# 6_dc_dc_5V_Payloads.net
KiCad netlist of a schematic drawn in Altium Designer
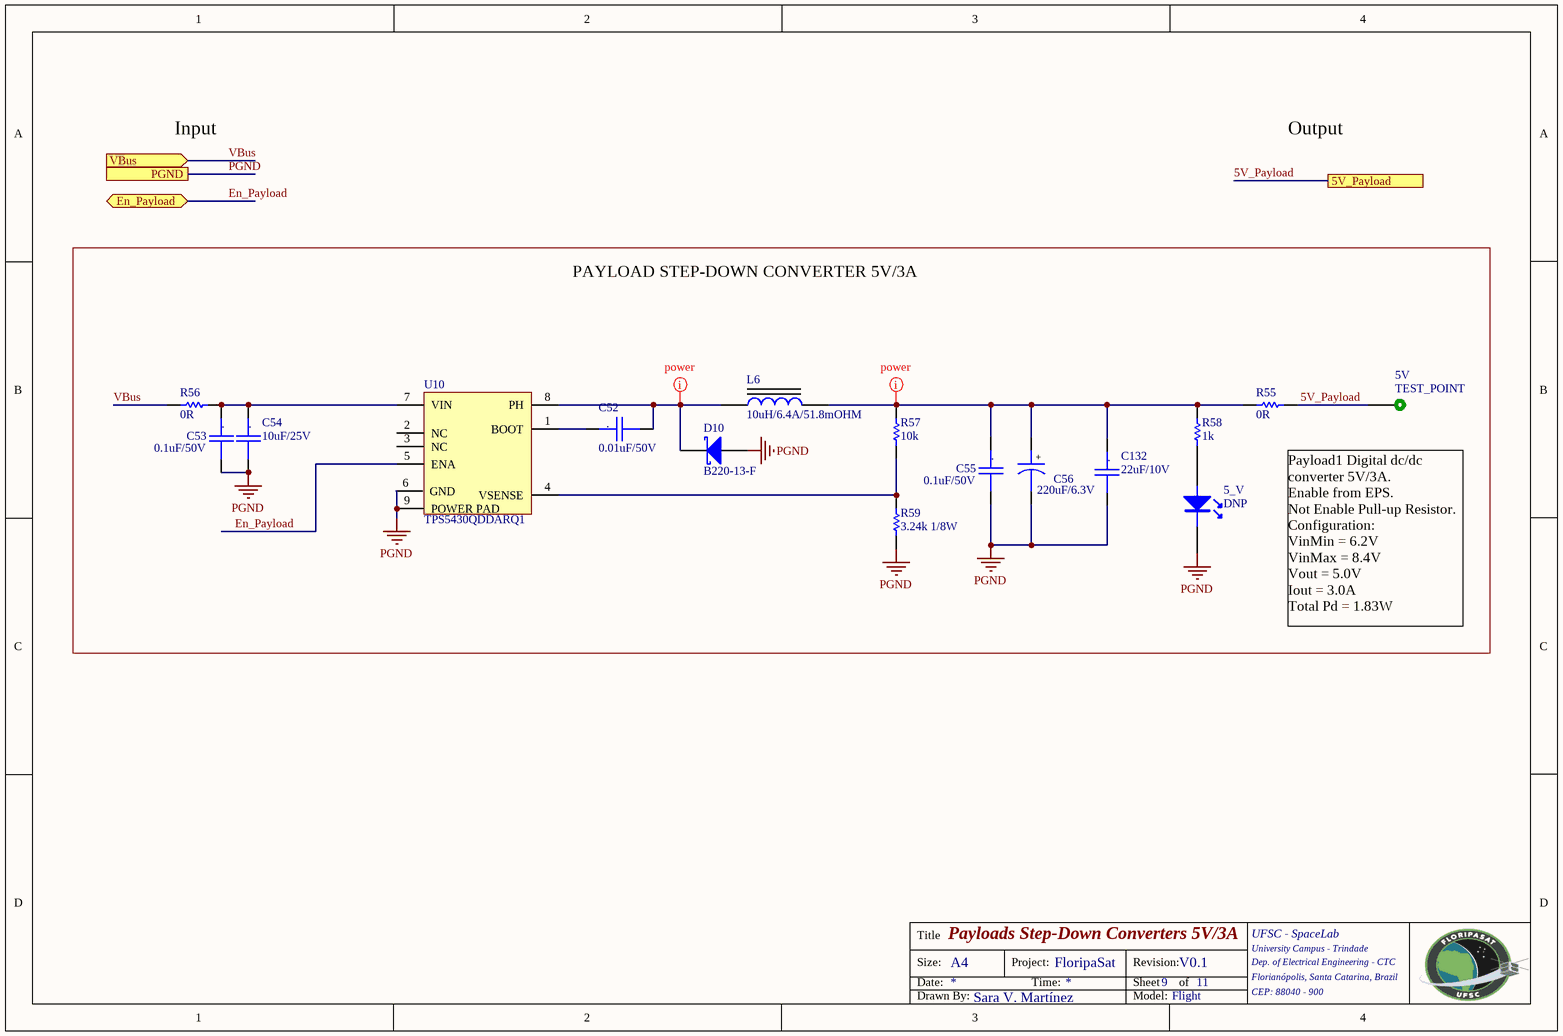
[diagram p0: 6_dc_dc_5V_Payloads.SchDoc]

(export (version "E")
  (design (tool "Eeschema 10.0.6"))
  (components
    (comp (ref "5V")
      (value "TEST_POINT")
      (footprint "TEST_POINT")
      (description "Test point")
      (libsource (lib "PCB_Project_FlightModel_EPS") (part "TEST_POINT"))
    )
    (comp (ref "5_V")
      (value "DNP")
      (footprint "0603-LED")
      (description "SMD Green LED")
      (fields (field (name "PARTNUMBER") "150060VS75000") (field (name "MANUFACTURER") "Wurth Electronics"))
      (libsource (lib "PCB_Project_FlightModel_EPS") (part "LED/G_0603"))
    )
    (comp (ref "C52")
      (value "0.01uF/50V")
      (footprint "CC0805")
      (description "CAP CER 0.01uF 50V 10% X7R 0805")
      (fields (field (name "PARTNUMBER") "08055C103KAT4A") (field (name "MANUFACTURER") "Kyocera AVX"))
      (libsource (lib "PCB_Project_FlightModel_EPS") (part "Cap_Cer_X7R_0.01uF_50V_0805"))
    )
    (comp (ref "C53")
      (value "0.1uF/50V")
      (footprint "CC0805")
      (description "CAP CER 0.1UF 50V 10% X7R 0805")
      (fields (field (name "PARTNUMBER") "CC0805KRX7R9BB104") (field (name "MANUFACTURER") "Yageo"))
      (libsource (lib "PCB_Project_FlightModel_EPS") (part "Cap_Cer_X7R_0.1uF_50V_0805"))
    )
    (comp (ref "C54")
      (value "10uF/25V")
      (footprint "CC1206")
      (description "CAP CER 10uF 25V 10% X7R 1206")
      (fields (field (name "PARTNUMBER") "GRM31CR71E106KA12L") (field (name "MANUFACTURER") "Murata"))
      (libsource (lib "PCB_Project_FlightModel_EPS") (part "Cap_Cer_X7R_10uF_25V_1206"))
    )
    (comp (ref "C55")
      (value "0.1uF/50V")
      (footprint "CC0805")
      (description "CAP CER 0.1UF 50V 10% X7R 0805")
      (fields (field (name "PARTNUMBER") "CC0805KRX7R9BB104") (field (name "MANUFACTURER") "Yageo"))
      (libsource (lib "PCB_Project_FlightModel_EPS") (part "Cap_Cer_X7R_0.1uF_50V_0805"))
    )
    (comp (ref "C56")
      (value "220uF/6.3V")
      (footprint "FloripaSatPcbLib:cc1210")
      (description "CAP Tantalum 220uF 6.3V 20% 1210")
      (fields (field (name "PARTNUMBER") "6TPE220MAZB") (field (name "MANUFACTURER") "Panasonic"))
      (libsource (lib "PCB_Project_FlightModel_EPS") (part "Cap_Tant_SMD_220uF_6.3V_1210"))
    )
    (comp (ref "C132")
      (value "22uF/10V")
      (footprint "CC1206")
      (description "CAP CER 22uF 10V 10% X7R 1206")
      (fields (field (name "PARTNUMBER") "GRM31CR71A226KE15L") (field (name "MANUFACTURER") "Murata"))
      (libsource (lib "PCB_Project_FlightModel_EPS") (part "Cap_Cer_X7R_22uF_10V_1206"))
    )
    (comp (ref "D10")
      (value "B220-13-F")
      (footprint "DO-214AA")
      (description "DIODE SCHOTTKY 20V 2A B220-13-F")
      (fields (field (name "MANUFACTURER") "Diodes"))
      (libsource (lib "PCB_Project_FlightModel_EPS") (part "DIODE_SCHOTTKY_20V_2A_MB220-13-F"))
    )
    (comp (ref "L6")
      (value "10uH/6.4A/51.8mOHM")
      (footprint "Ind_IHLP")
      (description "INDUCTOR 2.2UH 6.4A SMD")
      (fields (field (name "PARTNUMBER") "IHLP3232DZER100M11") (field (name "MANUFACTURER") "Vishay Dale"))
      (libsource (lib "PCB_Project_FlightModel_EPS") (part "IND_POWER_10uH_6.4A_51.8mR"))
    )
    (comp (ref "R55")
      (value "0R")
      (footprint "1206")
      (description "RES 0.0 OHM 3/4W JUMP 1206")
      (fields
        (field (name "PARTNUMBER") "HCJ1206ZT0R00")
        (field (name "MANUFACTURER") "Stackpole Electronics")
      )
      (libsource (lib "PCB_Project_FlightModel_EPS") (part "R0R_JUMPER_3/4W_1206"))
    )
    (comp (ref "R56")
      (value "0R")
      (footprint "1206")
      (description "RES 0.0 OHM 3/4W JUMP 1206")
      (fields
        (field (name "PARTNUMBER") "HCJ1206ZT0R00")
        (field (name "MANUFACTURER") "Stackpole Electronics")
      )
      (libsource (lib "PCB_Project_FlightModel_EPS") (part "R0R_JUMPER_3/4W_1206"))
    )
    (comp (ref "R57")
      (value "10k")
      (footprint "0805")
      (description "RES 10K OHM 1/8W 1%  0805")
      (fields (field (name "PARTNUMBER") "CRCW080510K0FKEA") (field (name "MANUFACTURER") "Vishay"))
      (libsource (lib "PCB_Project_FlightModel_EPS") (part "R10k_1%_1/8W_0805"))
    )
    (comp (ref "R58")
      (value "1k")
      (footprint "0603")
      (description "RES 1.0K OHM 1/8W 1% 0603")
      (fields (field (name "PARTNUMBER") "MCT06030C1001FP500") (field (name "MANUFACTURER") "Vishay"))
      (libsource (lib "PCB_Project_FlightModel_EPS") (part "R1.0k_1%_1/8W_0603"))
    )
    (comp (ref "R59")
      (value "3.24k 1/8W")
      (footprint "0805")
      (description "RES 3.24k OHM 1/8W 1% 0805 SMD")
      (fields (field (name "PARTNUMBER") "CRCW08053K24FKEA") (field (name "MANUFACTURER") "Vishay"))
      (libsource (lib "PCB_Project_FlightModel_EPS") (part "R3.24k_1%_1/8W_0805"))
    )
    (comp (ref "U10")
      (value "TPS5430QDDARQ1")
      (footprint "SO8 Power PAD")
      (fields (field (name "MANUFACTURER") "Texas Instruments"))
      (libsource (lib "PCB_Project_FlightModel_EPS") (part "TPS5430QDDARQ1"))
    )
  )
  (nets
    (net (code "1") (name "/5V_Payload") (class "Default")
      (node (ref "5V") (pin "1") (pinfunction "1_1") (pintype "passive"))
      (node (ref "R55") (pin "1") (pinfunction "1_1") (pintype "passive"))
    )
    (net (code "2") (name "/En_Payload") (class "Default")
      (node (ref "U10") (pin "5") (pinfunction "ENA_5") (pintype "passive"))
    )
    (net (code "3") (name "/VBus") (class "Default")
      (node (ref "R56") (pin "2") (pinfunction "2_2") (pintype "passive"))
    )
    (net (code "4") (name "Net-(5_V-A)") (class "Default")
      (node (ref "5_V") (pin "1") (pinfunction "A_1") (pintype "passive"))
      (node (ref "R58") (pin "2") (pinfunction "2_2") (pintype "passive"))
    )
    (net (code "5") (name "Net-(C132-Pad1)") (class "Default")
      (node (ref "C132") (pin "1") (pinfunction "1_1") (pintype "passive"))
      (node (ref "C55") (pin "1") (pinfunction "1_1") (pintype "passive"))
      (node (ref "C56") (pin "1") (pinfunction "1_1") (pintype "passive"))
      (node (ref "L6") (pin "2") (pinfunction "2_2") (pintype "passive"))
      (node (ref "R55") (pin "2") (pinfunction "2_2") (pintype "passive"))
      (node (ref "R57") (pin "2") (pinfunction "2_2") (pintype "passive"))
      (node (ref "R58") (pin "1") (pinfunction "1_1") (pintype "passive"))
    )
    (net (code "6") (name "Net-(D10-K)") (class "Default")
      (node (ref "C52") (pin "2") (pinfunction "2_2") (pintype "passive"))
      (node (ref "D10") (pin "1") (pinfunction "K_1") (pintype "passive"))
      (node (ref "L6") (pin "1") (pinfunction "1_1") (pintype "passive"))
      (node (ref "U10") (pin "8") (pinfunction "PH_8") (pintype "passive"))
    )
    (net (code "7") (name "Net-(U10-BOOT)") (class "Default")
      (node (ref "C52") (pin "1") (pinfunction "1_1") (pintype "passive"))
      (node (ref "U10") (pin "1") (pinfunction "BOOT_1") (pintype "passive"))
    )
    (net (code "8") (name "Net-(U10-VIN)") (class "Default")
      (node (ref "C53") (pin "1") (pinfunction "1_1") (pintype "passive"))
      (node (ref "C54") (pin "1") (pinfunction "1_1") (pintype "passive"))
      (node (ref "R56") (pin "1") (pinfunction "1_1") (pintype "passive"))
      (node (ref "U10") (pin "7") (pinfunction "VIN_7") (pintype "passive"))
    )
    (net (code "9") (name "Net-(U10-VSENSE)") (class "Default")
      (node (ref "R57") (pin "1") (pinfunction "1_1") (pintype "passive"))
      (node (ref "R59") (pin "2") (pinfunction "2_2") (pintype "passive"))
      (node (ref "U10") (pin "4") (pinfunction "VSENSE_4") (pintype "passive"))
    )
    (net (code "10") (name "PGND") (class "Default")
      (node (ref "5_V") (pin "2") (pinfunction "K_2") (pintype "passive"))
      (node (ref "C132") (pin "2") (pinfunction "2_2") (pintype "passive"))
      (node (ref "C53") (pin "2") (pinfunction "2_2") (pintype "passive"))
      (node (ref "C54") (pin "2") (pinfunction "2_2") (pintype "passive"))
      (node (ref "C55") (pin "2") (pinfunction "2_2") (pintype "passive"))
      (node (ref "C56") (pin "2") (pinfunction "2_2") (pintype "passive"))
      (node (ref "D10") (pin "2") (pinfunction "A_2") (pintype "passive"))
      (node (ref "R59") (pin "1") (pinfunction "1_1") (pintype "passive"))
      (node (ref "U10") (pin "6") (pinfunction "GND_6") (pintype "passive"))
      (node (ref "U10") (pin "9") (pinfunction "POWER_PAD_9") (pintype "passive"))
    )
    (net (code "11") (name "unconnected-(U10-NC-Pad2)") (class "Default")
      (node (ref "U10") (pin "2") (pinfunction "NC_2") (pintype "passive"))
    )
    (net (code "12") (name "unconnected-(U10-NC-Pad3)") (class "Default")
      (node (ref "U10") (pin "3") (pinfunction "NC_3") (pintype "passive"))
    )
  )
)
